# BRD161224.net
KiCad netlist of a schematic drawn in EAGLE
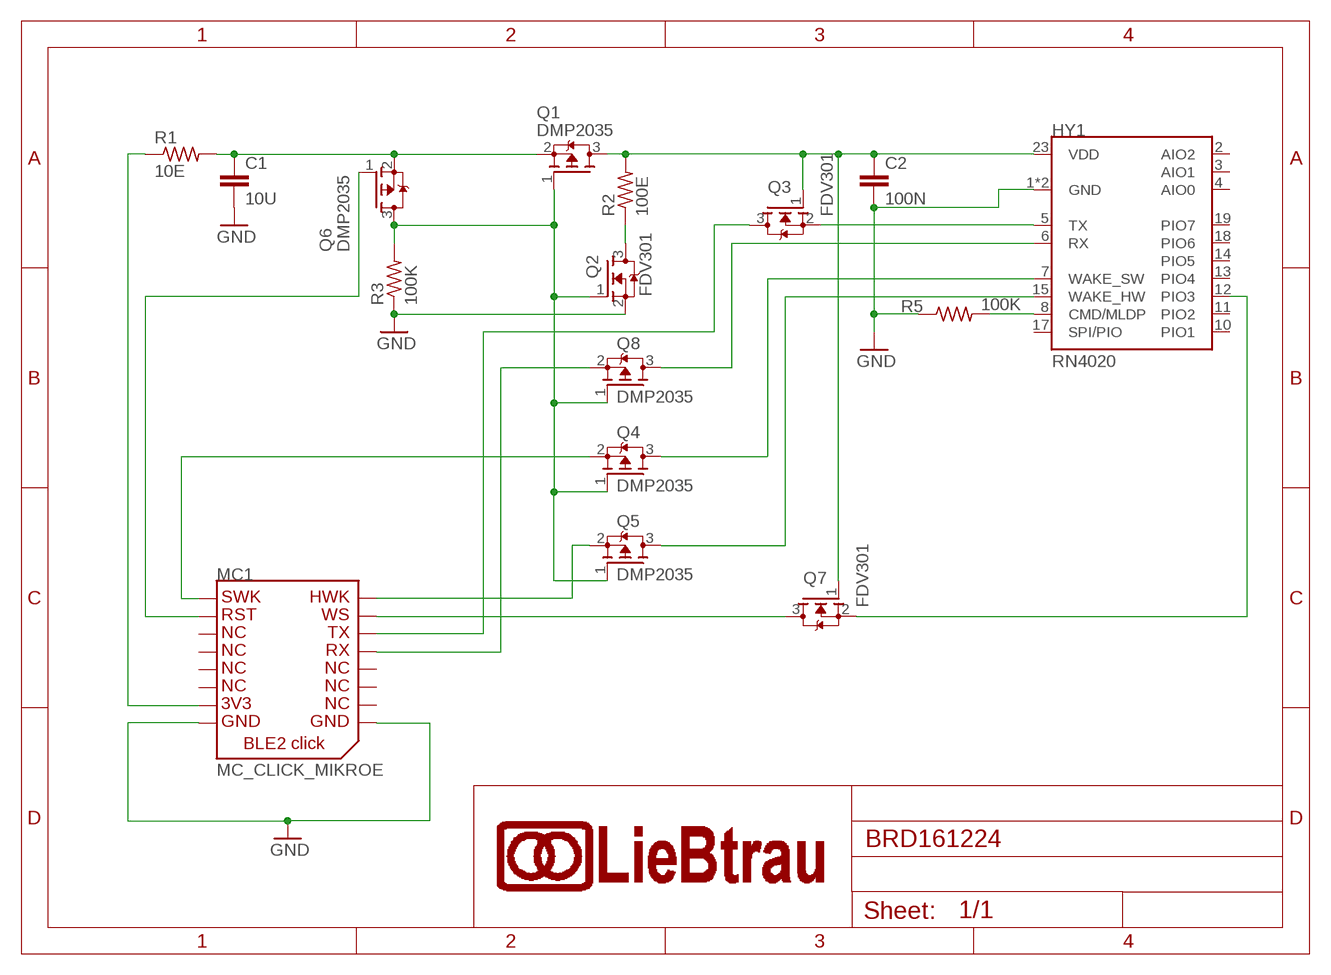
[diagram p0: schematic, sheet 1]

(export (version "E")
  (design (tool "Eeschema 10.0.6"))
  (components
    (comp (ref "C1")
      (value "10U")
      (footprint "eagle-import:CA_1206")
      (libsource (lib "eagle-import") (part "CA1206_10U_"))
    )
    (comp (ref "C2")
      (value "100N")
      (footprint "eagle-import:CA_1206")
      (libsource (lib "eagle-import") (part "CA1206_100N_"))
    )
    (comp (ref "HY1")
      (value "RN4020")
      (footprint "eagle-import:HY_BLE_RN4020")
      (libsource (lib "eagle-import") (part "HY_RF_BLE_RN4020"))
    )
    (comp (ref "MC1")
      (value "MC_CLICK_MIKROE")
      (footprint "eagle-import:MC_CLICK_MIKROE")
      (fields
        (field (name "AN") "AN")
        (field (name "RST") "RST")
        (field (name "CS") "CS")
        (field (name "SCK") "SCK")
        (field (name "MISO") "MISO")
        (field (name "MOSI") "MOSI")
        (field (name "3V3") "3V3")
        (field (name "5V") "5V")
        (field (name "PWM") "PWM")
        (field (name "RX") "RX")
        (field (name "INT") "INT")
        (field (name "TX") "TX")
        (field (name "SCL") "SCL")
        (field (name "SDA") "SDA")
        (field (name "5V_1") "NC")
        (field (name "AN_1") "SWK")
        (field (name "CS_1") "NC")
        (field (name "INT_1") "WS")
        (field (name "MISO_1") "NC")
        (field (name "MOSI_1") "NC")
        (field (name "PWM_1") "HWK")
        (field (name "SCK_1") "NC")
        (field (name "SCL_1") "NC")
        (field (name "SDA_1") "NC")
      )
      (libsource (lib "eagle-import") (part "MC_CLICK_MIKROE"))
    )
    (comp (ref "Q1")
      (value "DMP2035")
      (footprint "eagle-import:SC_SOT23")
      (libsource (lib "eagle-import") (part "TR_PMOSSOT23_DMP2035_"))
    )
    (comp (ref "Q2")
      (value "FDV301")
      (footprint "eagle-import:SC_SOT23")
      (libsource (lib "eagle-import") (part "TR_NMOSSOT23_FDV301_"))
    )
    (comp (ref "Q3")
      (value "FDV301")
      (footprint "eagle-import:SC_SOT23")
      (libsource (lib "eagle-import") (part "TR_NMOSSOT23_FDV301_"))
    )
    (comp (ref "Q4")
      (value "DMP2035")
      (footprint "eagle-import:SC_SOT23")
      (libsource (lib "eagle-import") (part "TR_PMOSSOT23_DMP2035_"))
    )
    (comp (ref "Q5")
      (value "DMP2035")
      (footprint "eagle-import:SC_SOT23")
      (libsource (lib "eagle-import") (part "TR_PMOSSOT23_DMP2035_"))
    )
    (comp (ref "Q6")
      (value "DMP2035")
      (footprint "eagle-import:SC_SOT23")
      (libsource (lib "eagle-import") (part "TR_PMOSSOT23_DMP2035_"))
    )
    (comp (ref "Q7")
      (value "FDV301")
      (footprint "eagle-import:SC_SOT23")
      (libsource (lib "eagle-import") (part "TR_NMOSSOT23_FDV301_"))
    )
    (comp (ref "Q8")
      (value "DMP2035")
      (footprint "eagle-import:SC_SOT23")
      (libsource (lib "eagle-import") (part "TR_PMOSSOT23_DMP2035_"))
    )
    (comp (ref "R1")
      (value "10E")
      (footprint "eagle-import:RE_1206")
      (libsource (lib "eagle-import") (part "RE1206_10E_"))
    )
    (comp (ref "R2")
      (value "100E")
      (footprint "eagle-import:RE_1206")
      (libsource (lib "eagle-import") (part "RE1206_100E_"))
    )
    (comp (ref "R3")
      (value "100K")
      (footprint "eagle-import:RE_1206")
      (libsource (lib "eagle-import") (part "RE1206_100K_"))
    )
    (comp (ref "R5")
      (value "100K")
      (footprint "eagle-import:RE_1206")
      (libsource (lib "eagle-import") (part "RE1206_100K_"))
    )
  )
  (nets
    (net (code "1") (name "GND") (class "Default")
      (node (ref "C1") (pin "2") (pinfunction "2_2") (pintype "passive"))
      (node (ref "C2") (pin "2") (pinfunction "2_2") (pintype "passive"))
      (node (ref "HY1") (pin "1") (pinfunction "GND_1") (pintype "bidirectional"))
      (node (ref "HY1") (pin "24") (pinfunction "GND_24") (pintype "bidirectional"))
      (node (ref "MC1") (pin "P$8") (pinfunction "8_P$8") (pintype "bidirectional"))
      (node (ref "MC1") (pin "P$9") (pinfunction "P$9_P$9") (pintype "bidirectional"))
      (node (ref "Q2") (pin "2") (pinfunction "S_2") (pintype "passive"))
      (node (ref "R3") (pin "1") (pinfunction "1_1") (pintype "passive"))
      (node (ref "R5") (pin "1") (pinfunction "1_1") (pintype "passive"))
    )
    (net (code "2") (name "Net-(HY1-CMD{slash}MLDP)") (class "Default")
      (node (ref "HY1") (pin "8") (pinfunction "CMD/MLDP_8") (pintype "bidirectional"))
      (node (ref "R5") (pin "2") (pinfunction "2_2") (pintype "passive"))
    )
    (net (code "3") (name "Net-(HY1-PIO3)") (class "Default")
      (node (ref "HY1") (pin "12") (pinfunction "PIO3_12") (pintype "bidirectional"))
      (node (ref "Q7") (pin "2") (pinfunction "S_2") (pintype "passive"))
    )
    (net (code "4") (name "Net-(HY1-RX)") (class "Default")
      (node (ref "HY1") (pin "6") (pinfunction "RX_6") (pintype "bidirectional"))
      (node (ref "Q8") (pin "3") (pinfunction "D_3") (pintype "passive"))
    )
    (net (code "5") (name "Net-(HY1-TX)") (class "Default")
      (node (ref "HY1") (pin "5") (pinfunction "TX_5") (pintype "bidirectional"))
      (node (ref "Q3") (pin "2") (pinfunction "S_2") (pintype "passive"))
    )
    (net (code "6") (name "Net-(HY1-VDD)") (class "Default")
      (node (ref "C2") (pin "1") (pinfunction "1_1") (pintype "passive"))
      (node (ref "HY1") (pin "23") (pinfunction "VDD_23") (pintype "bidirectional"))
      (node (ref "Q1") (pin "3") (pinfunction "D_3") (pintype "passive"))
      (node (ref "Q3") (pin "1") (pinfunction "G_1") (pintype "passive"))
      (node (ref "Q7") (pin "1") (pinfunction "G_1") (pintype "passive"))
      (node (ref "R2") (pin "2") (pinfunction "2_2") (pintype "passive"))
    )
    (net (code "7") (name "Net-(HY1-WAKE_HW)") (class "Default")
      (node (ref "HY1") (pin "15") (pinfunction "WAKE_HW_15") (pintype "bidirectional"))
      (node (ref "Q5") (pin "3") (pinfunction "D_3") (pintype "passive"))
    )
    (net (code "8") (name "Net-(HY1-WAKE_SW)") (class "Default")
      (node (ref "HY1") (pin "7") (pinfunction "WAKE_SW_7") (pintype "bidirectional"))
      (node (ref "Q4") (pin "3") (pinfunction "D_3") (pintype "passive"))
    )
    (net (code "9") (name "Net-(MC1-PadP$7)") (class "Default")
      (node (ref "MC1") (pin "P$7") (pinfunction "P$7_P$7") (pintype "bidirectional"))
      (node (ref "R1") (pin "1") (pinfunction "1_1") (pintype "passive"))
    )
    (net (code "10") (name "Net-(Q1-G)") (class "Default")
      (node (ref "Q1") (pin "1") (pinfunction "G_1") (pintype "passive"))
      (node (ref "Q2") (pin "1") (pinfunction "G_1") (pintype "passive"))
      (node (ref "Q4") (pin "1") (pinfunction "G_1") (pintype "passive"))
      (node (ref "Q5") (pin "1") (pinfunction "G_1") (pintype "passive"))
      (node (ref "Q6") (pin "3") (pinfunction "D_3") (pintype "passive"))
      (node (ref "Q8") (pin "1") (pinfunction "G_1") (pintype "passive"))
      (node (ref "R3") (pin "2") (pinfunction "2_2") (pintype "passive"))
    )
    (net (code "11") (name "Net-(Q1-S)") (class "Default")
      (node (ref "C1") (pin "1") (pinfunction "1_1") (pintype "passive"))
      (node (ref "Q1") (pin "2") (pinfunction "S_2") (pintype "passive"))
      (node (ref "Q6") (pin "2") (pinfunction "S_2") (pintype "passive"))
      (node (ref "R1") (pin "2") (pinfunction "2_2") (pintype "passive"))
    )
    (net (code "12") (name "Net-(Q2-D)") (class "Default")
      (node (ref "Q2") (pin "3") (pinfunction "D_3") (pintype "passive"))
      (node (ref "R2") (pin "1") (pinfunction "1_1") (pintype "passive"))
    )
    (net (code "13") (name "Net-(Q3-D)") (class "Default")
      (node (ref "MC1") (pin "P$14") (pinfunction "P$14_P$14") (pintype "bidirectional"))
      (node (ref "Q3") (pin "3") (pinfunction "D_3") (pintype "passive"))
    )
    (net (code "14") (name "Net-(Q4-S)") (class "Default")
      (node (ref "MC1") (pin "P$1") (pinfunction "P$1_P$1") (pintype "bidirectional"))
      (node (ref "Q4") (pin "2") (pinfunction "S_2") (pintype "passive"))
    )
    (net (code "15") (name "Net-(Q5-S)") (class "Default")
      (node (ref "MC1") (pin "P$16") (pinfunction "P$16_P$16") (pintype "bidirectional"))
      (node (ref "Q5") (pin "2") (pinfunction "S_2") (pintype "passive"))
    )
    (net (code "16") (name "Net-(Q6-G)") (class "Default")
      (node (ref "MC1") (pin "P$2") (pinfunction "P$2_P$2") (pintype "bidirectional"))
      (node (ref "Q6") (pin "1") (pinfunction "G_1") (pintype "passive"))
    )
    (net (code "17") (name "Net-(Q7-D)") (class "Default")
      (node (ref "MC1") (pin "P$15") (pinfunction "P$15_P$15") (pintype "bidirectional"))
      (node (ref "Q7") (pin "3") (pinfunction "D_3") (pintype "passive"))
    )
    (net (code "18") (name "Net-(Q8-S)") (class "Default")
      (node (ref "MC1") (pin "P$13") (pinfunction "P$13_P$13") (pintype "bidirectional"))
      (node (ref "Q8") (pin "2") (pinfunction "S_2") (pintype "passive"))
    )
    (net (code "19") (name "unconnected-(HY1-AIO0-Pad4)") (class "Default")
      (node (ref "HY1") (pin "4") (pinfunction "AIO0_4") (pintype "bidirectional"))
    )
    (net (code "20") (name "unconnected-(HY1-AIO1-Pad3)") (class "Default")
      (node (ref "HY1") (pin "3") (pinfunction "AIO1_3") (pintype "bidirectional"))
    )
    (net (code "21") (name "unconnected-(HY1-AIO2-Pad2)") (class "Default")
      (node (ref "HY1") (pin "2") (pinfunction "AIO2_2") (pintype "bidirectional"))
    )
    (net (code "22") (name "unconnected-(HY1-PIO1-Pad10)") (class "Default")
      (node (ref "HY1") (pin "10") (pinfunction "PIO1_10") (pintype "bidirectional"))
    )
    (net (code "23") (name "unconnected-(HY1-PIO2-Pad11)") (class "Default")
      (node (ref "HY1") (pin "11") (pinfunction "PIO2_11") (pintype "bidirectional"))
    )
    (net (code "24") (name "unconnected-(HY1-PIO4-Pad13)") (class "Default")
      (node (ref "HY1") (pin "13") (pinfunction "PIO4_13") (pintype "bidirectional"))
    )
    (net (code "25") (name "unconnected-(HY1-PIO5-Pad14)") (class "Default")
      (node (ref "HY1") (pin "14") (pinfunction "PIO5_14") (pintype "bidirectional"))
    )
    (net (code "26") (name "unconnected-(HY1-PIO6-Pad18)") (class "Default")
      (node (ref "HY1") (pin "18") (pinfunction "PIO6_18") (pintype "bidirectional"))
    )
    (net (code "27") (name "unconnected-(HY1-PIO7-Pad19)") (class "Default")
      (node (ref "HY1") (pin "19") (pinfunction "PIO7_19") (pintype "bidirectional"))
    )
    (net (code "28") (name "unconnected-(HY1-SPI{slash}PIO-Pad17)") (class "Default")
      (node (ref "HY1") (pin "17") (pinfunction "SPI/PIO_17") (pintype "bidirectional"))
    )
    (net (code "29") (name "unconnected-(MC1-PadP$3)") (class "Default")
      (node (ref "MC1") (pin "P$3") (pinfunction "P$3_P$3") (pintype "bidirectional"))
    )
    (net (code "30") (name "unconnected-(MC1-PadP$4)") (class "Default")
      (node (ref "MC1") (pin "P$4") (pinfunction "P$4_P$4") (pintype "bidirectional"))
    )
    (net (code "31") (name "unconnected-(MC1-PadP$5)") (class "Default")
      (node (ref "MC1") (pin "P$5") (pinfunction "P$5_P$5") (pintype "bidirectional"))
    )
    (net (code "32") (name "unconnected-(MC1-PadP$6)") (class "Default")
      (node (ref "MC1") (pin "P$6") (pinfunction "P$6_P$6") (pintype "bidirectional"))
    )
    (net (code "33") (name "unconnected-(MC1-PadP$10)") (class "Default")
      (node (ref "MC1") (pin "P$10") (pinfunction "P$10_P$10") (pintype "bidirectional"))
    )
    (net (code "34") (name "unconnected-(MC1-PadP$11)") (class "Default")
      (node (ref "MC1") (pin "P$11") (pinfunction "P$11_P$11") (pintype "bidirectional"))
    )
    (net (code "35") (name "unconnected-(MC1-PadP$12)") (class "Default")
      (node (ref "MC1") (pin "P$12") (pinfunction "P$12_P$12") (pintype "bidirectional"))
    )
  )
)
